# CARTE_E-STOP.net
KiCad netlist of a schematic drawn in EAGLE
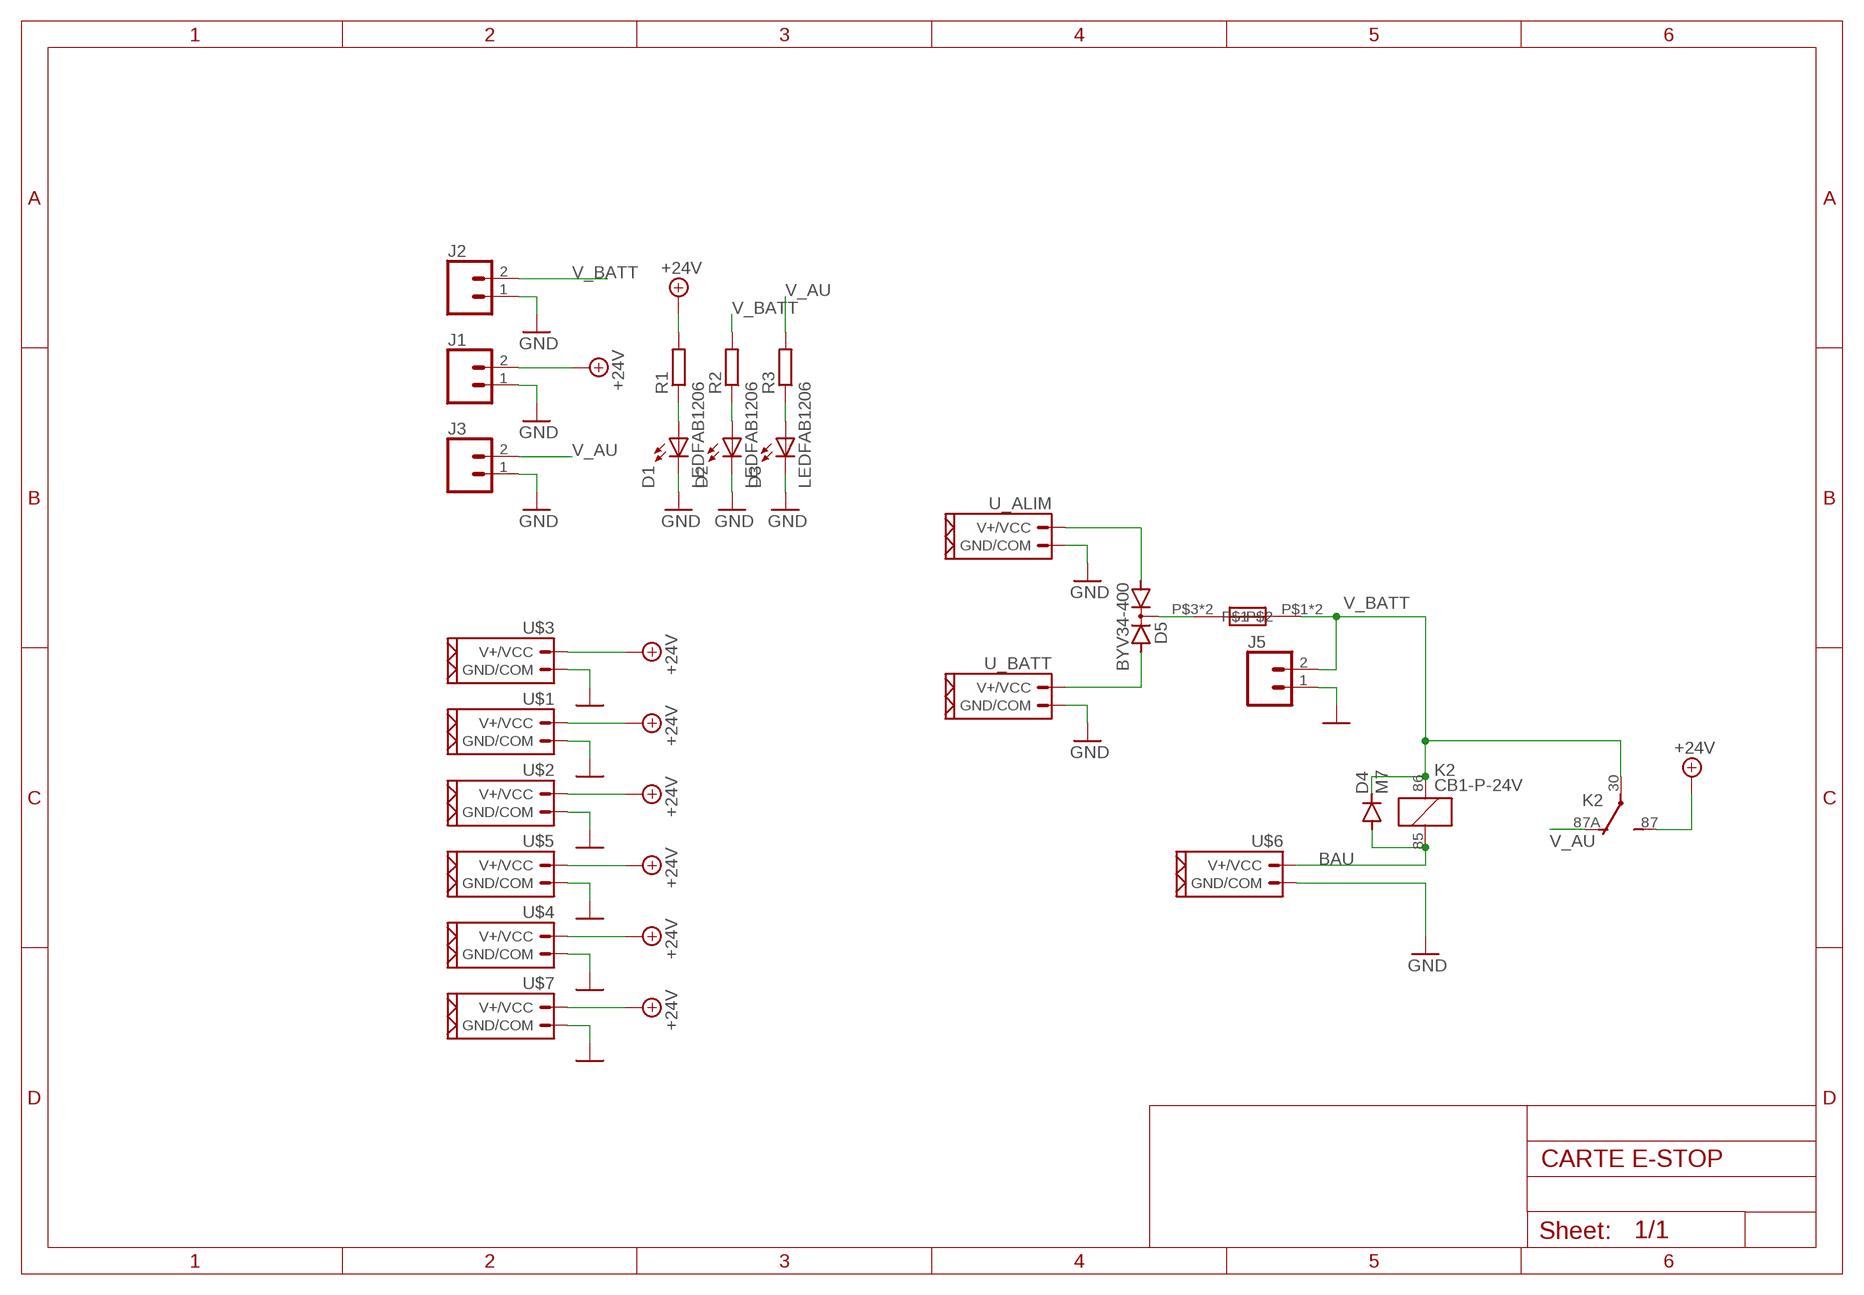
[diagram p0: schematic, sheet 1]

(export (version "E")
  (design (tool "Eeschema 10.0.6"))
  (components
    (comp (ref "D1")
      (value "LEDFAB1206")
      (footprint "eagle-import:LED1206FAB")
      (libsource (lib "eagle-import") (part "LEDFAB1206"))
    )
    (comp (ref "D2")
      (value "LEDFAB1206")
      (footprint "eagle-import:LED1206FAB")
      (libsource (lib "eagle-import") (part "LEDFAB1206"))
    )
    (comp (ref "D3")
      (value "LEDFAB1206")
      (footprint "eagle-import:LED1206FAB")
      (libsource (lib "eagle-import") (part "LEDFAB1206"))
    )
    (comp (ref "D4")
      (value "M7")
      (footprint "eagle-import:SMA-DO214AC")
      (libsource (lib "eagle-import") (part "GF1"))
    )
    (comp (ref "D5")
      (value "BYV34-400")
      (footprint "eagle-import:TO220ABS")
      (libsource (lib "eagle-import") (part "BYV32"))
    )
    (comp (ref "J1")
      (value "CONN_02POLAR")
      (footprint "eagle-import:MOLEX-1X2")
      (libsource (lib "eagle-import") (part "CONN_02POLAR"))
    )
    (comp (ref "J2")
      (value "CONN_02POLAR")
      (footprint "eagle-import:MOLEX-1X2")
      (libsource (lib "eagle-import") (part "CONN_02POLAR"))
    )
    (comp (ref "J3")
      (value "CONN_02POLAR")
      (footprint "eagle-import:MOLEX-1X2")
      (libsource (lib "eagle-import") (part "CONN_02POLAR"))
    )
    (comp (ref "J5")
      (value "CONN_02POLAR")
      (footprint "eagle-import:MOLEX-1X2")
      (libsource (lib "eagle-import") (part "CONN_02POLAR"))
    )
    (comp (ref "K2")
      (value "CB1-P-24V")
      (footprint "eagle-import:CB1")
      (fields (field (name "MF") "AROMAT/ MATSUSHITA"))
      (libsource (lib "eagle-import") (part "CB1-P-24V"))
    )
    (comp (ref "R1")
      (value "R-EU_M1206")
      (footprint "eagle-import:M1206")
      (libsource (lib "eagle-import") (part "R-EU_M1206"))
    )
    (comp (ref "R2")
      (value "R-EU_M1206")
      (footprint "eagle-import:M1206")
      (libsource (lib "eagle-import") (part "R-EU_M1206"))
    )
    (comp (ref "R3")
      (value "R-EU_M1206")
      (footprint "eagle-import:M1206")
      (libsource (lib "eagle-import") (part "R-EU_M1206"))
    )
    (comp (ref "U$1")
      (value "CONN_02_PUIXT30")
      (footprint "eagle-import:XT30_FEMALE")
      (libsource (lib "eagle-import") (part "CONN_02_PUIXT30"))
    )
    (comp (ref "U$2")
      (value "CONN_02_PUIXT30")
      (footprint "eagle-import:XT30_FEMALE")
      (libsource (lib "eagle-import") (part "CONN_02_PUIXT30"))
    )
    (comp (ref "U$3")
      (value "CONN_02_PUIXT30")
      (footprint "eagle-import:XT30_FEMALE")
      (libsource (lib "eagle-import") (part "CONN_02_PUIXT30"))
    )
    (comp (ref "U$4")
      (value "CONN_02_PUIXT30")
      (footprint "eagle-import:XT30_FEMALE")
      (libsource (lib "eagle-import") (part "CONN_02_PUIXT30"))
    )
    (comp (ref "U$5")
      (value "CONN_02_PUIXT30")
      (footprint "eagle-import:XT30_FEMALE")
      (libsource (lib "eagle-import") (part "CONN_02_PUIXT30"))
    )
    (comp (ref "U$6")
      (value "CONN_02_PUI")
      (footprint "eagle-import:NSK396-2C")
      (libsource (lib "eagle-import") (part "CONN_02_PUI"))
    )
    (comp (ref "U$7")
      (value "CONN_02_PUIXT30")
      (footprint "eagle-import:XT30_FEMALE")
      (libsource (lib "eagle-import") (part "CONN_02_PUIXT30"))
    )
    (comp (ref "U$8")
      (value "AUTOMOTIVE_FUSE3557-2")
      (footprint "eagle-import:3557-2")
      (libsource (lib "eagle-import") (part "AUTOMOTIVE_FUSE3557-2"))
    )
    (comp (ref "U_ALIM")
      (value "CONN_02_PUIXT60")
      (footprint "eagle-import:XT60")
      (libsource (lib "eagle-import") (part "CONN_02_PUIXT60"))
    )
    (comp (ref "U_BATT")
      (value "CONN_02_PUIXT60")
      (footprint "eagle-import:XT60")
      (libsource (lib "eagle-import") (part "CONN_02_PUIXT60"))
    )
  )
  (nets
    (net (code "1") (name "+24V") (class "Default")
      (node (ref "J1") (pin "2") (pinfunction "2_2") (pintype "passive"))
      (node (ref "K2") (pin "87") (pinfunction "S_87") (pintype "passive"))
      (node (ref "R1") (pin "2") (pinfunction "2_2") (pintype "passive"))
      (node (ref "U$1") (pin "P$1") (pinfunction "V+/VCC_P$1") (pintype "passive"))
      (node (ref "U$2") (pin "P$1") (pinfunction "V+/VCC_P$1") (pintype "passive"))
      (node (ref "U$3") (pin "P$1") (pinfunction "V+/VCC_P$1") (pintype "passive"))
      (node (ref "U$4") (pin "P$1") (pinfunction "V+/VCC_P$1") (pintype "passive"))
      (node (ref "U$5") (pin "P$1") (pinfunction "V+/VCC_P$1") (pintype "passive"))
      (node (ref "U$7") (pin "P$1") (pinfunction "V+/VCC_P$1") (pintype "passive"))
    )
    (net (code "2") (name "/BAU") (class "Default")
      (node (ref "D4") (pin "A") (pinfunction "A_A") (pintype "passive"))
      (node (ref "K2") (pin "85") (pinfunction "2_85") (pintype "passive"))
      (node (ref "U$6") (pin "P$2") (pinfunction "V+/VCC_P$2") (pintype "passive"))
    )
    (net (code "3") (name "/V_AU") (class "Default")
      (node (ref "J3") (pin "2") (pinfunction "2_2") (pintype "passive"))
      (node (ref "K2") (pin "87A") (pinfunction "O_87A") (pintype "passive"))
      (node (ref "R3") (pin "2") (pinfunction "2_2") (pintype "passive"))
    )
    (net (code "4") (name "/V_BATT") (class "Default")
      (node (ref "D4") (pin "K") (pinfunction "C_K") (pintype "passive"))
      (node (ref "J2") (pin "2") (pinfunction "2_2") (pintype "passive"))
      (node (ref "J5") (pin "2") (pinfunction "2_2") (pintype "passive"))
      (node (ref "K2") (pin "30") (pinfunction "P_30") (pintype "passive"))
      (node (ref "K2") (pin "86") (pinfunction "1_86") (pintype "passive"))
      (node (ref "R2") (pin "2") (pinfunction "2_2") (pintype "passive"))
      (node (ref "U$8") (pin "P$1") (pinfunction "P$1_P$1") (pintype "bidirectional"))
      (node (ref "U$8") (pin "P$2") (pinfunction "P$1_P$2") (pintype "bidirectional"))
    )
    (net (code "5") (name "GND") (class "Default")
      (node (ref "D1") (pin "2") (pinfunction "C_2") (pintype "passive"))
      (node (ref "D2") (pin "2") (pinfunction "C_2") (pintype "passive"))
      (node (ref "D3") (pin "2") (pinfunction "C_2") (pintype "passive"))
      (node (ref "J1") (pin "1") (pinfunction "1_1") (pintype "passive"))
      (node (ref "J2") (pin "1") (pinfunction "1_1") (pintype "passive"))
      (node (ref "J3") (pin "1") (pinfunction "1_1") (pintype "passive"))
      (node (ref "J5") (pin "1") (pinfunction "1_1") (pintype "passive"))
      (node (ref "U$1") (pin "P$2") (pinfunction "GND/COM_P$2") (pintype "passive"))
      (node (ref "U$2") (pin "P$2") (pinfunction "GND/COM_P$2") (pintype "passive"))
      (node (ref "U$3") (pin "P$2") (pinfunction "GND/COM_P$2") (pintype "passive"))
      (node (ref "U$4") (pin "P$2") (pinfunction "GND/COM_P$2") (pintype "passive"))
      (node (ref "U$5") (pin "P$2") (pinfunction "GND/COM_P$2") (pintype "passive"))
      (node (ref "U$6") (pin "P$1") (pinfunction "GND/COM_P$1") (pintype "passive"))
      (node (ref "U$7") (pin "P$2") (pinfunction "GND/COM_P$2") (pintype "passive"))
      (node (ref "U_ALIM") (pin "P$2") (pinfunction "GND/COM_P$2") (pintype "passive"))
      (node (ref "U_BATT") (pin "P$2") (pinfunction "GND/COM_P$2") (pintype "passive"))
    )
    (net (code "6") (name "Net-(D1-A)") (class "Default")
      (node (ref "D1") (pin "1") (pinfunction "A_1") (pintype "passive"))
      (node (ref "R1") (pin "1") (pinfunction "1_1") (pintype "passive"))
    )
    (net (code "7") (name "Net-(D2-A)") (class "Default")
      (node (ref "D2") (pin "1") (pinfunction "A_1") (pintype "passive"))
      (node (ref "R2") (pin "1") (pinfunction "1_1") (pintype "passive"))
    )
    (net (code "8") (name "Net-(D3-A)") (class "Default")
      (node (ref "D3") (pin "1") (pinfunction "A_1") (pintype "passive"))
      (node (ref "R3") (pin "1") (pinfunction "1_1") (pintype "passive"))
    )
    (net (code "9") (name "Net-(D5-PadC)") (class "Default")
      (node (ref "D5") (pin "C") (pinfunction "C_C") (pintype "passive"))
      (node (ref "U$8") (pin "P$3") (pinfunction "P$2_P$3") (pintype "bidirectional"))
      (node (ref "U$8") (pin "P$4") (pinfunction "P$2_P$4") (pintype "bidirectional"))
    )
    (net (code "10") (name "Net-(U_ALIM-V+{slash}VCC)") (class "Default")
      (node (ref "D5") (pin "A1") (pinfunction "A1_A1") (pintype "passive"))
      (node (ref "U_ALIM") (pin "P$1") (pinfunction "V+/VCC_P$1") (pintype "passive"))
    )
    (net (code "11") (name "Net-(U_BATT-V+{slash}VCC)") (class "Default")
      (node (ref "D5") (pin "A2") (pinfunction "A2_A2") (pintype "passive"))
      (node (ref "U_BATT") (pin "P$1") (pinfunction "V+/VCC_P$1") (pintype "passive"))
    )
  )
)
